# Microduino_v0_1.net
KiCad netlist of a schematic drawn in EAGLE
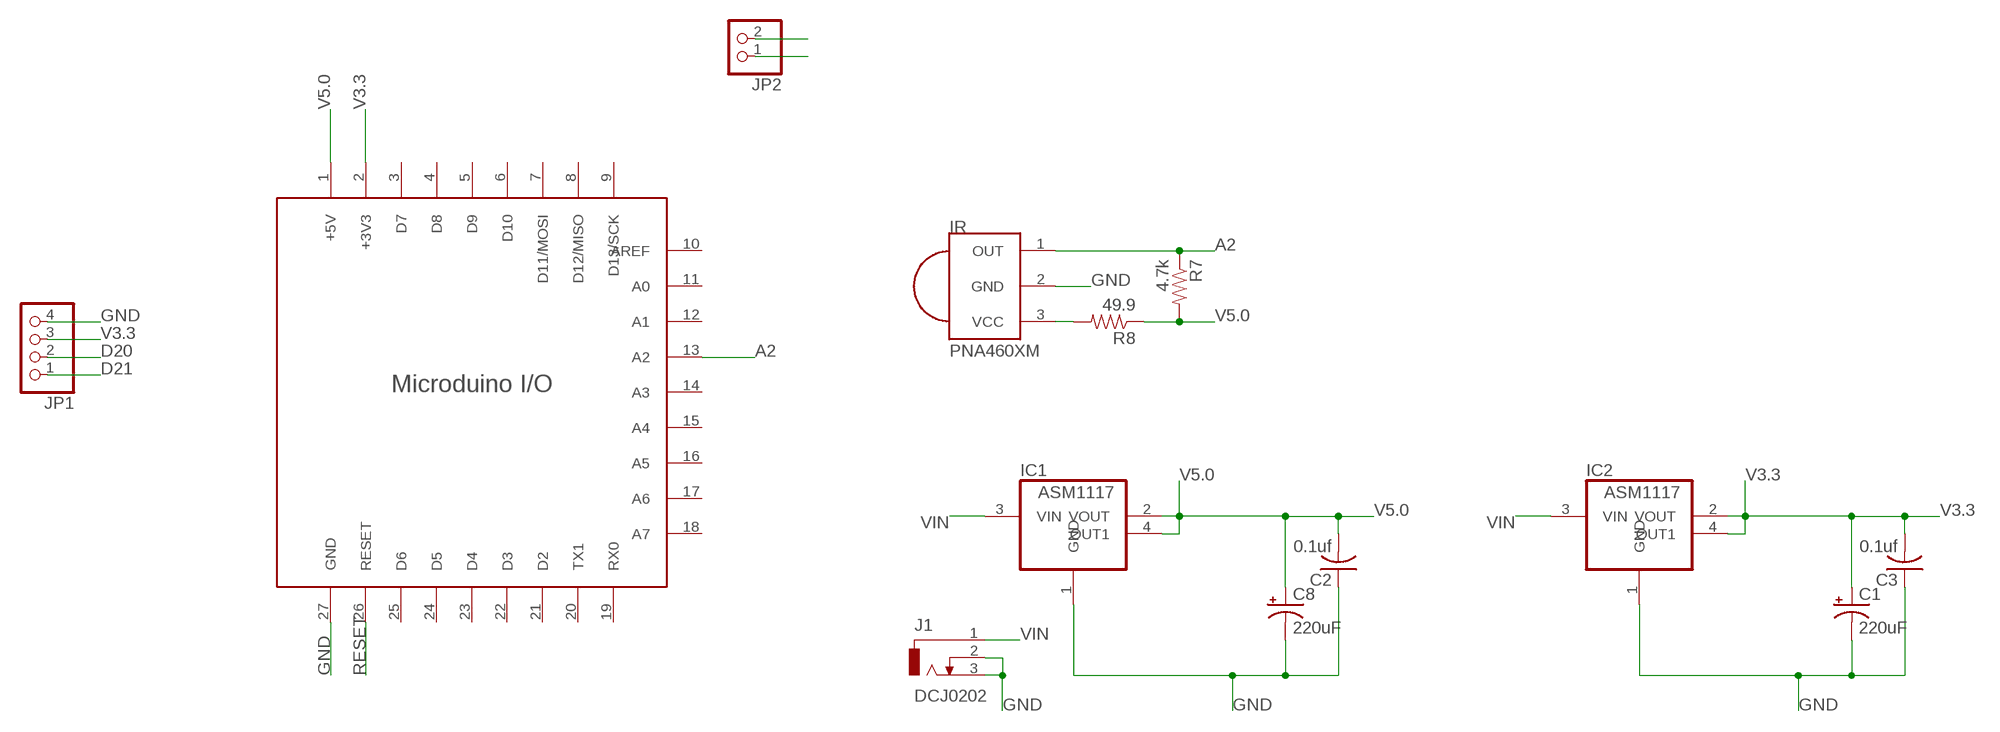
[diagram p0: schematic, sheet 1]

(export (version "E")
  (design (tool "Eeschema 10.0.6"))
  (components
    (comp (ref "C1")
      (value "220uF")
      (footprint "eagle-import:E2,5-5")
      (libsource (lib "eagle-import") (part "CPOL-USE2.5-5"))
    )
    (comp (ref "C2")
      (value "0.1uf")
      (footprint "eagle-import:C025-024X044")
      (libsource (lib "eagle-import") (part "C-US025-024X044"))
    )
    (comp (ref "C3")
      (value "0.1uf")
      (footprint "eagle-import:C025-024X044")
      (libsource (lib "eagle-import") (part "C-US025-024X044"))
    )
    (comp (ref "C8")
      (value "220uF")
      (footprint "eagle-import:E2,5-5")
      (libsource (lib "eagle-import") (part "CPOL-USE2.5-5"))
    )
    (comp (ref "IC1")
      (value "ASM1117")
      (footprint "eagle-import:SOT223")
      (fields (field (name "MPN") "REG1117"))
      (libsource (lib "eagle-import") (part "ASM1117"))
    )
    (comp (ref "IC2")
      (value "ASM1117")
      (footprint "eagle-import:SOT223")
      (fields (field (name "MPN") "REG1117"))
      (libsource (lib "eagle-import") (part "ASM1117"))
    )
    (comp (ref "IR")
      (value "PNA460XM")
      (footprint "eagle-import:PNA460XM")
      (libsource (lib "eagle-import") (part "PNA460XM"))
    )
    (comp (ref "J1")
      (value "DCJ0202")
      (footprint "eagle-import:DCJ0202")
      (libsource (lib "eagle-import") (part "DCJ0202"))
    )
    (comp (ref "JP1")
      (value "PINHD-1X4")
      (footprint "eagle-import:1X04")
      (libsource (lib "eagle-import") (part "PINHD-1X4"))
    )
    (comp (ref "JP2")
      (value "PINHD-1X2")
      (footprint "eagle-import:1X02")
      (libsource (lib "eagle-import") (part "PINHD-1X2"))
    )
    (comp (ref "R7")
      (value "4.7k")
      (footprint "eagle-import:AXIAL-0.3")
      (libsource (lib "eagle-import") (part "RESISTORPTH1"))
    )
    (comp (ref "R8")
      (value "49.9")
      (footprint "eagle-import:AXIAL-0.3")
      (libsource (lib "eagle-import") (part "RESISTORPTH1"))
    )
    (comp (ref "U$1")
      (value "PING-MICRDUINO-DZ/1009")
      (footprint "eagle-import:PIN-MICRODUINO-1009")
      (libsource (lib "eagle-import") (part "PING-MICRDUINO-DZ/1009"))
    )
  )
  (nets
    (net (code "1") (name "/A2") (class "Default")
      (node (ref "IR") (pin "1") (pinfunction "OUT_1") (pintype "output"))
      (node (ref "R7") (pin "P$1") (pinfunction "1_P$1") (pintype "passive"))
      (node (ref "U$1") (pin "13") (pinfunction "A2_13") (pintype "bidirectional"))
    )
    (net (code "2") (name "/D20") (class "Default")
      (node (ref "JP1") (pin "2") (pinfunction "2_2") (pintype "passive"))
      (node (ref "JP2") (pin "2") (pinfunction "2_2") (pintype "passive"))
    )
    (net (code "3") (name "/D21") (class "Default")
      (node (ref "JP1") (pin "1") (pinfunction "1_1") (pintype "passive"))
      (node (ref "JP2") (pin "1") (pinfunction "1_1") (pintype "passive"))
    )
    (net (code "4") (name "/GND") (class "Default")
      (node (ref "C1") (pin "-") (pinfunction "-_-") (pintype "passive"))
      (node (ref "C2") (pin "1") (pinfunction "1_1") (pintype "passive"))
      (node (ref "C3") (pin "1") (pinfunction "1_1") (pintype "passive"))
      (node (ref "C8") (pin "-") (pinfunction "-_-") (pintype "passive"))
      (node (ref "IC1") (pin "1") (pinfunction "GND_1") (pintype "power_in"))
      (node (ref "IC2") (pin "1") (pinfunction "GND_1") (pintype "power_in"))
      (node (ref "IR") (pin "2") (pinfunction "GND_2") (pintype "power_in"))
      (node (ref "J1") (pin "2") (pinfunction "2_2") (pintype "passive"))
      (node (ref "J1") (pin "3") (pinfunction "3_3") (pintype "passive"))
      (node (ref "JP1") (pin "4") (pinfunction "4_4") (pintype "passive"))
      (node (ref "U$1") (pin "27") (pinfunction "GND_27") (pintype "bidirectional"))
    )
    (net (code "5") (name "/RESET") (class "Default")
      (node (ref "U$1") (pin "26") (pinfunction "RESET_26") (pintype "bidirectional"))
    )
    (net (code "6") (name "/V3.3") (class "Default")
      (node (ref "C1") (pin "+") (pinfunction "+_+") (pintype "passive"))
      (node (ref "C3") (pin "2") (pinfunction "2_2") (pintype "passive"))
      (node (ref "IC2") (pin "2") (pinfunction "VOUT_2") (pintype "output"))
      (node (ref "IC2") (pin "4") (pinfunction "OUT1_4") (pintype "bidirectional"))
      (node (ref "JP1") (pin "3") (pinfunction "3_3") (pintype "passive"))
      (node (ref "U$1") (pin "2") (pinfunction "+3V3_2") (pintype "bidirectional"))
    )
    (net (code "7") (name "/V5.0") (class "Default")
      (node (ref "C2") (pin "2") (pinfunction "2_2") (pintype "passive"))
      (node (ref "C8") (pin "+") (pinfunction "+_+") (pintype "passive"))
      (node (ref "IC1") (pin "2") (pinfunction "VOUT_2") (pintype "output"))
      (node (ref "IC1") (pin "4") (pinfunction "OUT1_4") (pintype "bidirectional"))
      (node (ref "R7") (pin "P$2") (pinfunction "2_P$2") (pintype "passive"))
      (node (ref "R8") (pin "P$1") (pinfunction "1_P$1") (pintype "passive"))
      (node (ref "U$1") (pin "1") (pinfunction "+5V_1") (pintype "bidirectional"))
    )
    (net (code "8") (name "/VIN") (class "Default")
      (node (ref "IC1") (pin "3") (pinfunction "VIN_3") (pintype "input"))
      (node (ref "IC2") (pin "3") (pinfunction "VIN_3") (pintype "input"))
      (node (ref "J1") (pin "1") (pinfunction "1_1") (pintype "passive"))
    )
    (net (code "9") (name "Net-(IR-VCC)") (class "Default")
      (node (ref "IR") (pin "3") (pinfunction "VCC_3") (pintype "power_in"))
      (node (ref "R8") (pin "P$2") (pinfunction "2_P$2") (pintype "passive"))
    )
    (net (code "10") (name "unconnected-(U$1-A0-Pad11)") (class "Default")
      (node (ref "U$1") (pin "11") (pinfunction "A0_11") (pintype "bidirectional"))
    )
    (net (code "11") (name "unconnected-(U$1-A1-Pad12)") (class "Default")
      (node (ref "U$1") (pin "12") (pinfunction "A1_12") (pintype "bidirectional"))
    )
    (net (code "12") (name "unconnected-(U$1-A3-Pad14)") (class "Default")
      (node (ref "U$1") (pin "14") (pinfunction "A3_14") (pintype "bidirectional"))
    )
    (net (code "13") (name "unconnected-(U$1-A4-Pad15)") (class "Default")
      (node (ref "U$1") (pin "15") (pinfunction "A4_15") (pintype "bidirectional"))
    )
    (net (code "14") (name "unconnected-(U$1-A5-Pad16)") (class "Default")
      (node (ref "U$1") (pin "16") (pinfunction "A5_16") (pintype "bidirectional"))
    )
    (net (code "15") (name "unconnected-(U$1-A6-Pad17)") (class "Default")
      (node (ref "U$1") (pin "17") (pinfunction "A6_17") (pintype "bidirectional"))
    )
    (net (code "16") (name "unconnected-(U$1-A7-Pad18)") (class "Default")
      (node (ref "U$1") (pin "18") (pinfunction "A7_18") (pintype "bidirectional"))
    )
    (net (code "17") (name "unconnected-(U$1-AREF-Pad10)") (class "Default")
      (node (ref "U$1") (pin "10") (pinfunction "AREF_10") (pintype "bidirectional"))
    )
    (net (code "18") (name "unconnected-(U$1-D2-Pad21)") (class "Default")
      (node (ref "U$1") (pin "21") (pinfunction "D2_21") (pintype "bidirectional"))
    )
    (net (code "19") (name "unconnected-(U$1-D3-Pad22)") (class "Default")
      (node (ref "U$1") (pin "22") (pinfunction "D3_22") (pintype "bidirectional"))
    )
    (net (code "20") (name "unconnected-(U$1-D4-Pad23)") (class "Default")
      (node (ref "U$1") (pin "23") (pinfunction "D4_23") (pintype "bidirectional"))
    )
    (net (code "21") (name "unconnected-(U$1-D5-Pad24)") (class "Default")
      (node (ref "U$1") (pin "24") (pinfunction "D5_24") (pintype "bidirectional"))
    )
    (net (code "22") (name "unconnected-(U$1-D6-Pad25)") (class "Default")
      (node (ref "U$1") (pin "25") (pinfunction "D6_25") (pintype "bidirectional"))
    )
    (net (code "23") (name "unconnected-(U$1-D7-Pad3)") (class "Default")
      (node (ref "U$1") (pin "3") (pinfunction "D7_3") (pintype "bidirectional"))
    )
    (net (code "24") (name "unconnected-(U$1-D8-Pad4)") (class "Default")
      (node (ref "U$1") (pin "4") (pinfunction "D8_4") (pintype "bidirectional"))
    )
    (net (code "25") (name "unconnected-(U$1-D9-Pad5)") (class "Default")
      (node (ref "U$1") (pin "5") (pinfunction "D9_5") (pintype "bidirectional"))
    )
    (net (code "26") (name "unconnected-(U$1-D10-Pad6)") (class "Default")
      (node (ref "U$1") (pin "6") (pinfunction "D10_6") (pintype "bidirectional"))
    )
    (net (code "27") (name "unconnected-(U$1-D11{slash}MOSI-Pad7)") (class "Default")
      (node (ref "U$1") (pin "7") (pinfunction "D11/MOSI_7") (pintype "bidirectional"))
    )
    (net (code "28") (name "unconnected-(U$1-D12{slash}MISO-Pad8)") (class "Default")
      (node (ref "U$1") (pin "8") (pinfunction "D12/MISO_8") (pintype "bidirectional"))
    )
    (net (code "29") (name "unconnected-(U$1-D13{slash}SCK-Pad9)") (class "Default")
      (node (ref "U$1") (pin "9") (pinfunction "D13/SCK_9") (pintype "bidirectional"))
    )
    (net (code "30") (name "unconnected-(U$1-RX0-Pad19)") (class "Default")
      (node (ref "U$1") (pin "19") (pinfunction "RX0_19") (pintype "bidirectional"))
    )
    (net (code "31") (name "unconnected-(U$1-TX1-Pad20)") (class "Default")
      (node (ref "U$1") (pin "20") (pinfunction "TX1_20") (pintype "bidirectional"))
    )
  )
)
